# sloth_final.net
KiCad netlist of a schematic drawn in EAGLE
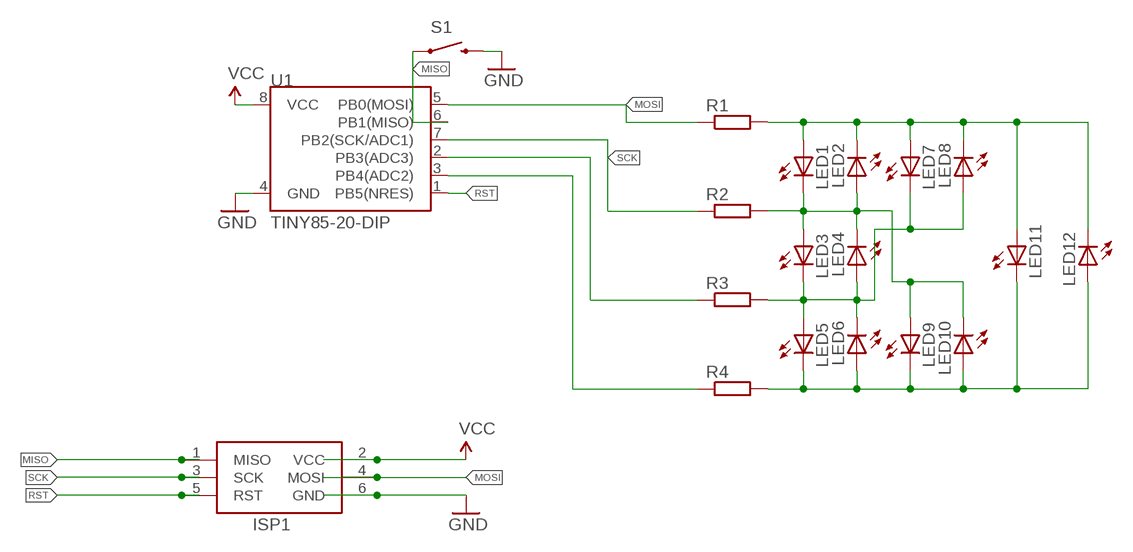
[diagram p0: schematic, sheet 1]

(export (version "E")
  (design (tool "Eeschema 10.0.6"))
  (components
    (comp (ref "ISP1")
      (value "AVRISP-BOX")
      (footprint "eagle-import:AVRISP-BOX")
      (libsource (lib "eagle-import") (part "AVRISP-BOX"))
    )
    (comp (ref "LED1")
      (value "LEDCHIP-LED0805")
      (footprint "eagle-import:CHIP-LED0805")
      (libsource (lib "eagle-import") (part "LEDCHIP-LED0805"))
    )
    (comp (ref "LED2")
      (value "LEDCHIP-LED0805")
      (footprint "eagle-import:CHIP-LED0805")
      (libsource (lib "eagle-import") (part "LEDCHIP-LED0805"))
    )
    (comp (ref "LED3")
      (value "LEDCHIP-LED0805")
      (footprint "eagle-import:CHIP-LED0805")
      (libsource (lib "eagle-import") (part "LEDCHIP-LED0805"))
    )
    (comp (ref "LED4")
      (value "LEDCHIP-LED0805")
      (footprint "eagle-import:CHIP-LED0805")
      (libsource (lib "eagle-import") (part "LEDCHIP-LED0805"))
    )
    (comp (ref "LED5")
      (value "LEDCHIP-LED0805")
      (footprint "eagle-import:CHIP-LED0805")
      (libsource (lib "eagle-import") (part "LEDCHIP-LED0805"))
    )
    (comp (ref "LED6")
      (value "LEDCHIP-LED0805")
      (footprint "eagle-import:CHIP-LED0805")
      (libsource (lib "eagle-import") (part "LEDCHIP-LED0805"))
    )
    (comp (ref "LED7")
      (value "LEDCHIP-LED0805")
      (footprint "eagle-import:CHIP-LED0805")
      (libsource (lib "eagle-import") (part "LEDCHIP-LED0805"))
    )
    (comp (ref "LED8")
      (value "LEDCHIP-LED0805")
      (footprint "eagle-import:CHIP-LED0805")
      (libsource (lib "eagle-import") (part "LEDCHIP-LED0805"))
    )
    (comp (ref "LED9")
      (value "LEDCHIP-LED0805")
      (footprint "eagle-import:CHIP-LED0805")
      (libsource (lib "eagle-import") (part "LEDCHIP-LED0805"))
    )
    (comp (ref "LED10")
      (value "LEDCHIP-LED0805")
      (footprint "eagle-import:CHIP-LED0805")
      (libsource (lib "eagle-import") (part "LEDCHIP-LED0805"))
    )
    (comp (ref "LED11")
      (value "LEDCHIP-LED0805")
      (footprint "eagle-import:CHIP-LED0805")
      (libsource (lib "eagle-import") (part "LEDCHIP-LED0805"))
    )
    (comp (ref "LED12")
      (value "LEDCHIP-LED0805")
      (footprint "eagle-import:CHIP-LED0805")
      (libsource (lib "eagle-import") (part "LEDCHIP-LED0805"))
    )
    (comp (ref "R1")
      (value "R-EU_R0805")
      (footprint "eagle-import:R0805")
      (libsource (lib "eagle-import") (part "R-EU_R0805"))
    )
    (comp (ref "R2")
      (value "R-EU_R0805")
      (footprint "eagle-import:R0805")
      (libsource (lib "eagle-import") (part "R-EU_R0805"))
    )
    (comp (ref "R3")
      (value "R-EU_R0805")
      (footprint "eagle-import:R0805")
      (libsource (lib "eagle-import") (part "R-EU_R0805"))
    )
    (comp (ref "R4")
      (value "R-EU_R0805")
      (footprint "eagle-import:R0805")
      (libsource (lib "eagle-import") (part "R-EU_R0805"))
    )
    (comp (ref "S1")
      (value "SWITCH-MOMENTARY-2PTH")
      (footprint "eagle-import:TACTILE-PTH")
      (libsource (lib "eagle-import") (part "SWITCH-MOMENTARY-2PTH"))
    )
    (comp (ref "U1")
      (value "TINY85-20-DIP")
      (footprint "eagle-import:DIP08")
      (libsource (lib "eagle-import") (part "ATTINY45TINY85-20-DIP"))
    )
  )
  (nets
    (net (code "1") (name "GND") (class "Default")
      (node (ref "ISP1") (pin "6") (pinfunction "GND_6") (pintype "power_in"))
      (node (ref "S1") (pin "3") (pinfunction "2_3") (pintype "passive"))
      (node (ref "U1") (pin "4") (pinfunction "GND_4") (pintype "bidirectional"))
    )
    (net (code "2") (name "MISO") (class "Default")
      (node (ref "ISP1") (pin "1") (pinfunction "MISO_1") (pintype "input"))
      (node (ref "S1") (pin "1") (pinfunction "1_1") (pintype "passive"))
      (node (ref "U1") (pin "6") (pinfunction "PB1(MISO)_6") (pintype "bidirectional"))
    )
    (net (code "3") (name "MOSI") (class "Default")
      (node (ref "ISP1") (pin "4") (pinfunction "MOSI_4") (pintype "output"))
      (node (ref "R1") (pin "1") (pinfunction "1_1") (pintype "passive"))
      (node (ref "U1") (pin "5") (pinfunction "PB0(MOSI)_5") (pintype "bidirectional"))
    )
    (net (code "4") (name "Net-(LED1-PadA)") (class "Default")
      (node (ref "LED1") (pin "A") (pinfunction "A_A") (pintype "passive"))
      (node (ref "LED11") (pin "A") (pinfunction "A_A") (pintype "passive"))
      (node (ref "LED12") (pin "C") (pinfunction "C_C") (pintype "passive"))
      (node (ref "LED2") (pin "C") (pinfunction "C_C") (pintype "passive"))
      (node (ref "LED7") (pin "A") (pinfunction "A_A") (pintype "passive"))
      (node (ref "LED8") (pin "C") (pinfunction "C_C") (pintype "passive"))
      (node (ref "R1") (pin "2") (pinfunction "2_2") (pintype "passive"))
    )
    (net (code "5") (name "Net-(LED1-PadC)") (class "Default")
      (node (ref "LED1") (pin "C") (pinfunction "C_C") (pintype "passive"))
      (node (ref "LED10") (pin "C") (pinfunction "C_C") (pintype "passive"))
      (node (ref "LED2") (pin "A") (pinfunction "A_A") (pintype "passive"))
      (node (ref "LED3") (pin "A") (pinfunction "A_A") (pintype "passive"))
      (node (ref "LED4") (pin "C") (pinfunction "C_C") (pintype "passive"))
      (node (ref "LED9") (pin "A") (pinfunction "A_A") (pintype "passive"))
      (node (ref "R2") (pin "2") (pinfunction "2_2") (pintype "passive"))
    )
    (net (code "6") (name "Net-(LED3-PadC)") (class "Default")
      (node (ref "LED3") (pin "C") (pinfunction "C_C") (pintype "passive"))
      (node (ref "LED4") (pin "A") (pinfunction "A_A") (pintype "passive"))
      (node (ref "LED5") (pin "A") (pinfunction "A_A") (pintype "passive"))
      (node (ref "LED6") (pin "C") (pinfunction "C_C") (pintype "passive"))
      (node (ref "LED7") (pin "C") (pinfunction "C_C") (pintype "passive"))
      (node (ref "LED8") (pin "A") (pinfunction "A_A") (pintype "passive"))
      (node (ref "R3") (pin "2") (pinfunction "2_2") (pintype "passive"))
    )
    (net (code "7") (name "Net-(LED10-PadA)") (class "Default")
      (node (ref "LED10") (pin "A") (pinfunction "A_A") (pintype "passive"))
      (node (ref "LED11") (pin "C") (pinfunction "C_C") (pintype "passive"))
      (node (ref "LED12") (pin "A") (pinfunction "A_A") (pintype "passive"))
      (node (ref "LED5") (pin "C") (pinfunction "C_C") (pintype "passive"))
      (node (ref "LED6") (pin "A") (pinfunction "A_A") (pintype "passive"))
      (node (ref "LED9") (pin "C") (pinfunction "C_C") (pintype "passive"))
      (node (ref "R4") (pin "2") (pinfunction "2_2") (pintype "passive"))
    )
    (net (code "8") (name "Net-(U1-PB3(ADC3))") (class "Default")
      (node (ref "R3") (pin "1") (pinfunction "1_1") (pintype "passive"))
      (node (ref "U1") (pin "2") (pinfunction "PB3(ADC3)_2") (pintype "bidirectional"))
    )
    (net (code "9") (name "Net-(U1-PB4(ADC2))") (class "Default")
      (node (ref "R4") (pin "1") (pinfunction "1_1") (pintype "passive"))
      (node (ref "U1") (pin "3") (pinfunction "PB4(ADC2)_3") (pintype "bidirectional"))
    )
    (net (code "10") (name "RST") (class "Default")
      (node (ref "ISP1") (pin "5") (pinfunction "RST_5") (pintype "output"))
      (node (ref "U1") (pin "1") (pinfunction "PB5(NRES)_1") (pintype "bidirectional"))
    )
    (net (code "11") (name "SCK") (class "Default")
      (node (ref "ISP1") (pin "3") (pinfunction "SCK_3") (pintype "output"))
      (node (ref "R2") (pin "1") (pinfunction "1_1") (pintype "passive"))
      (node (ref "U1") (pin "7") (pinfunction "PB2(SCK/ADC1)_7") (pintype "bidirectional"))
    )
    (net (code "12") (name "VCC") (class "Default")
      (node (ref "ISP1") (pin "2") (pinfunction "VCC_2") (pintype "power_in"))
      (node (ref "U1") (pin "8") (pinfunction "VCC_8") (pintype "bidirectional"))
    )
  )
)
